# braids_v50.net
KiCad netlist of a schematic drawn in EAGLE
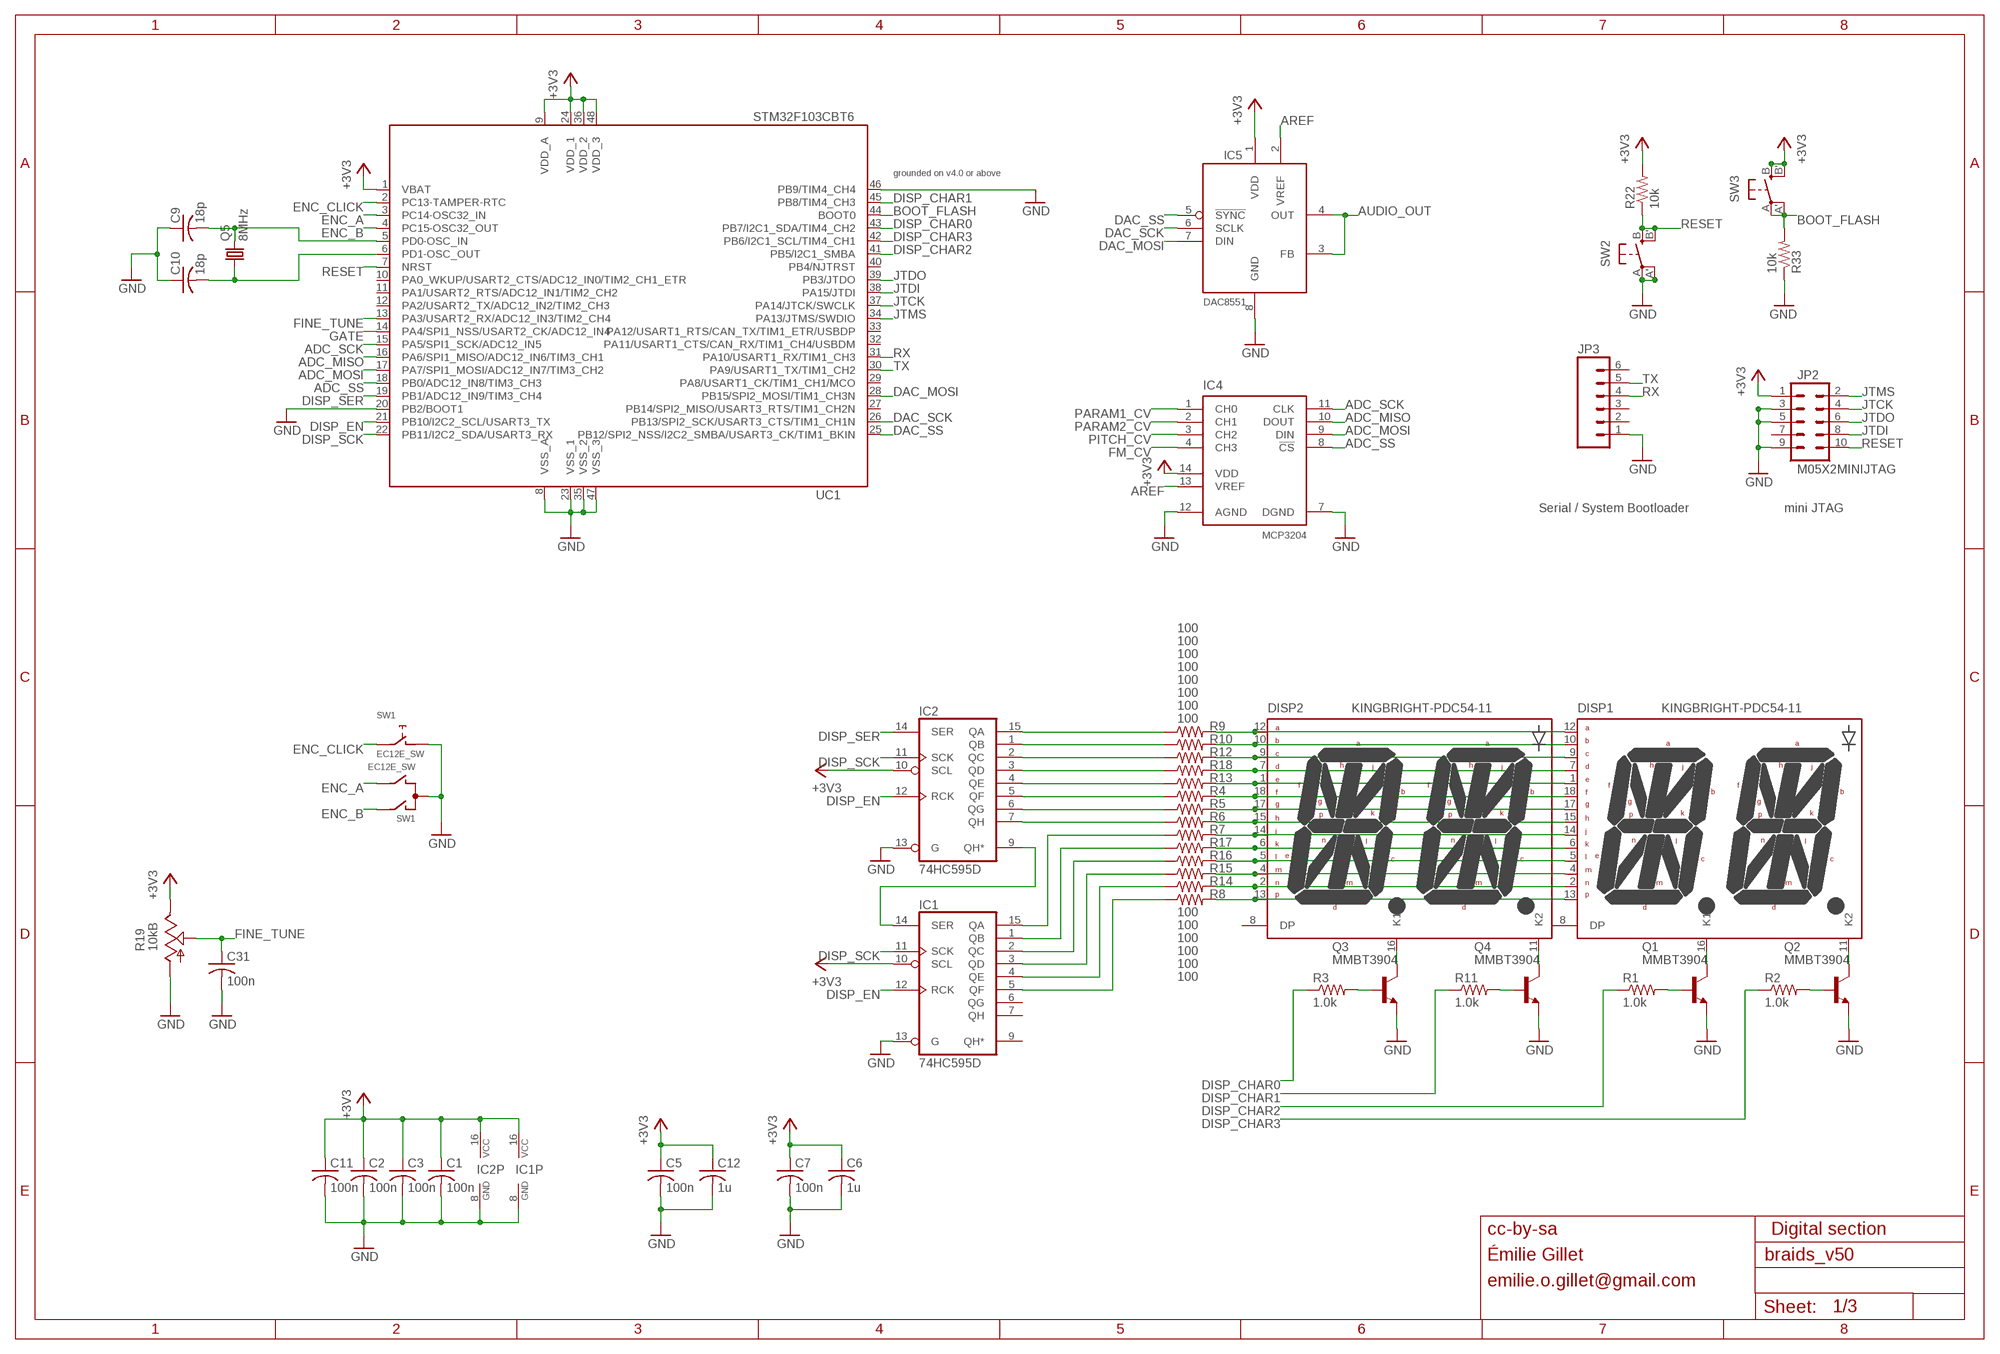
[diagram p0: schematic, sheet 1]
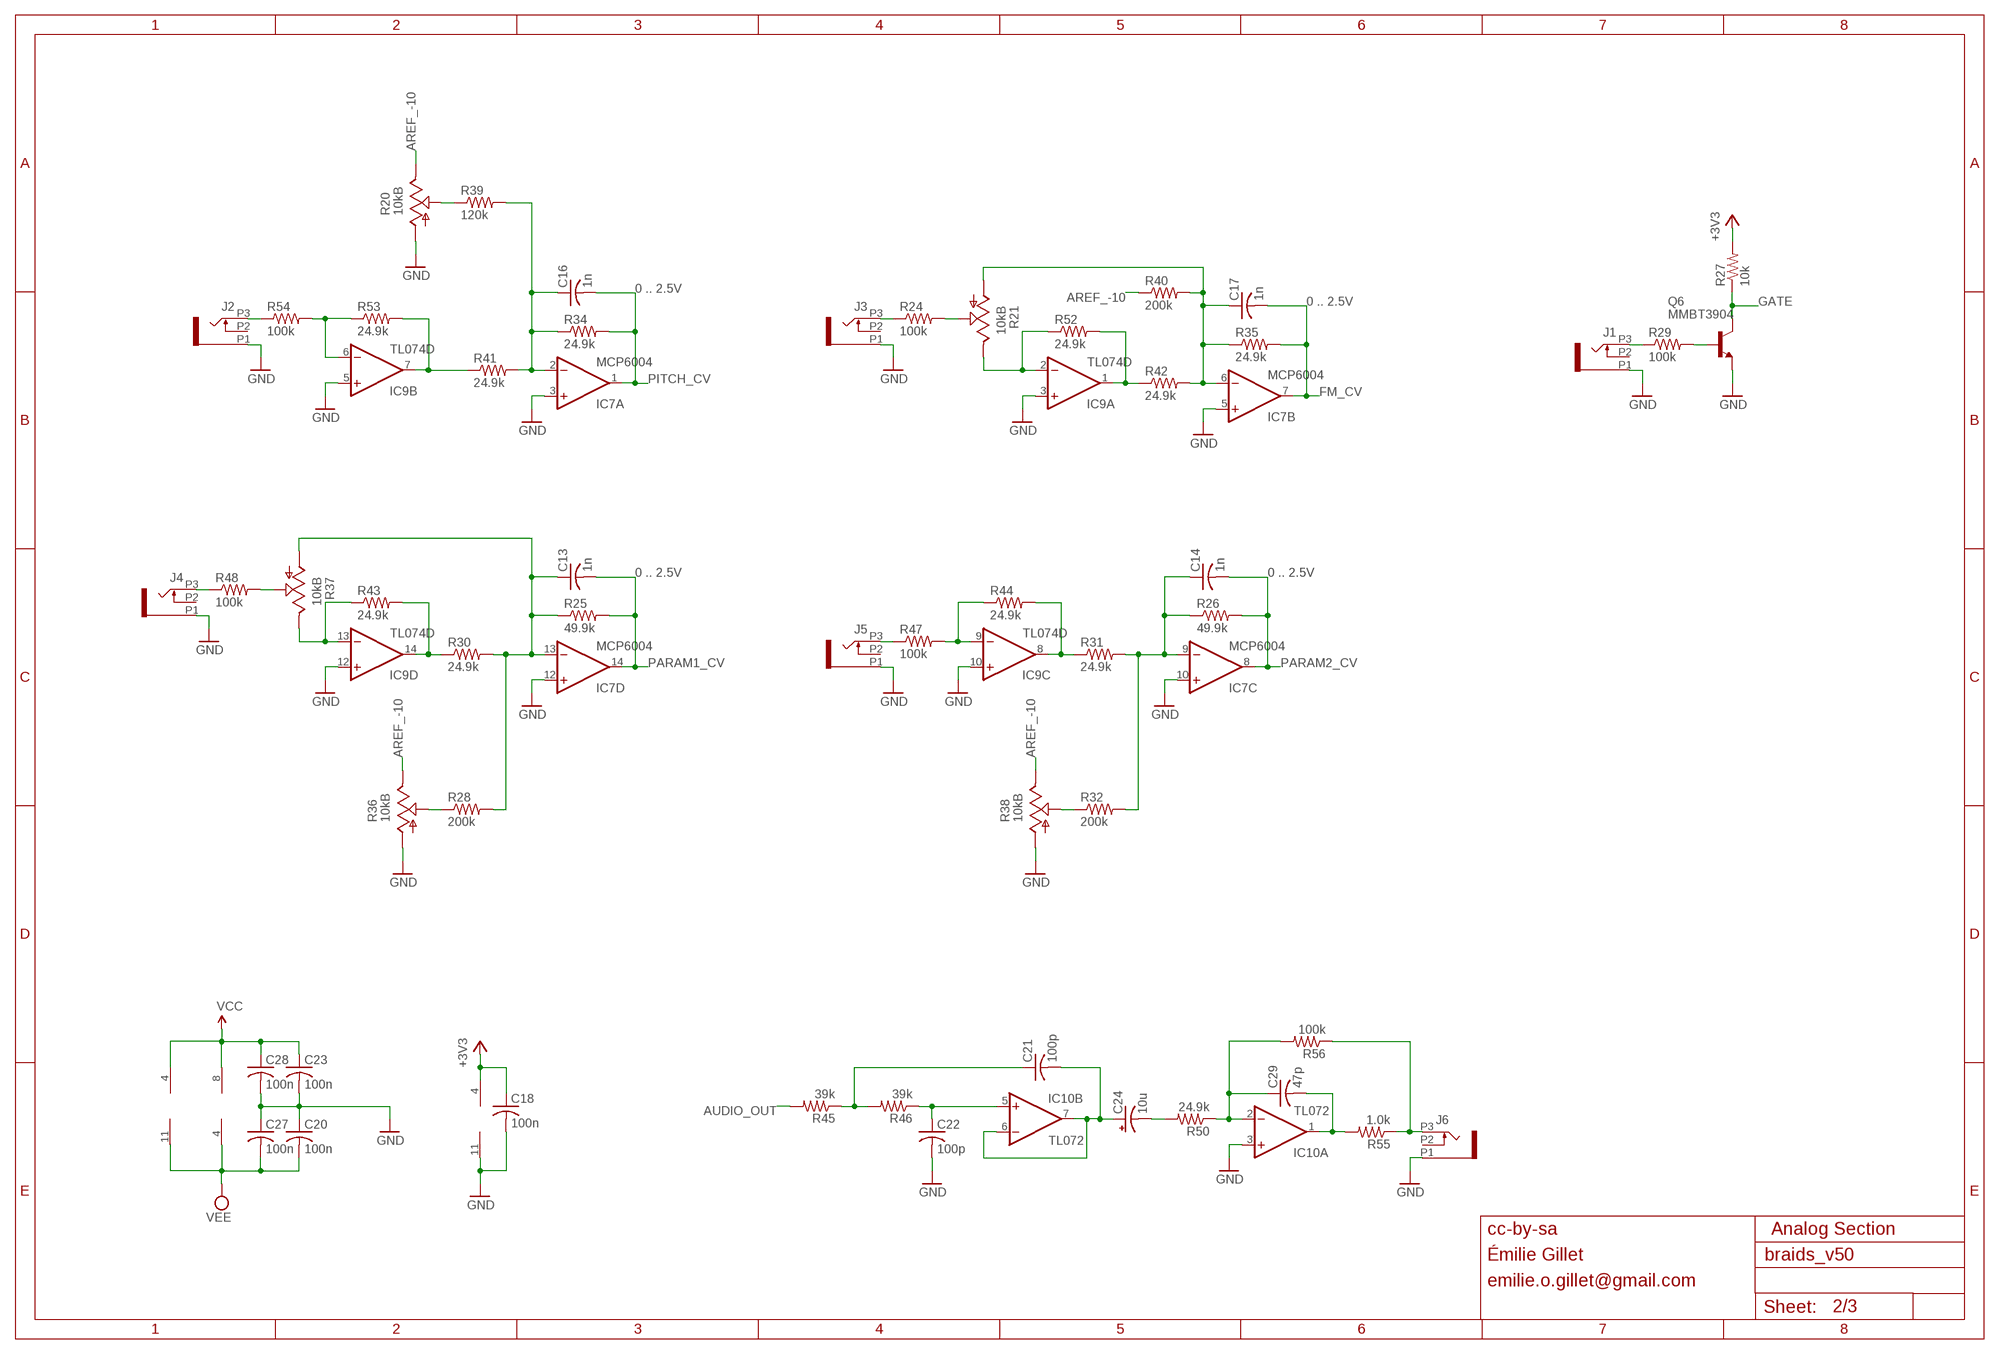
[diagram p1: schematic, sheet 2]
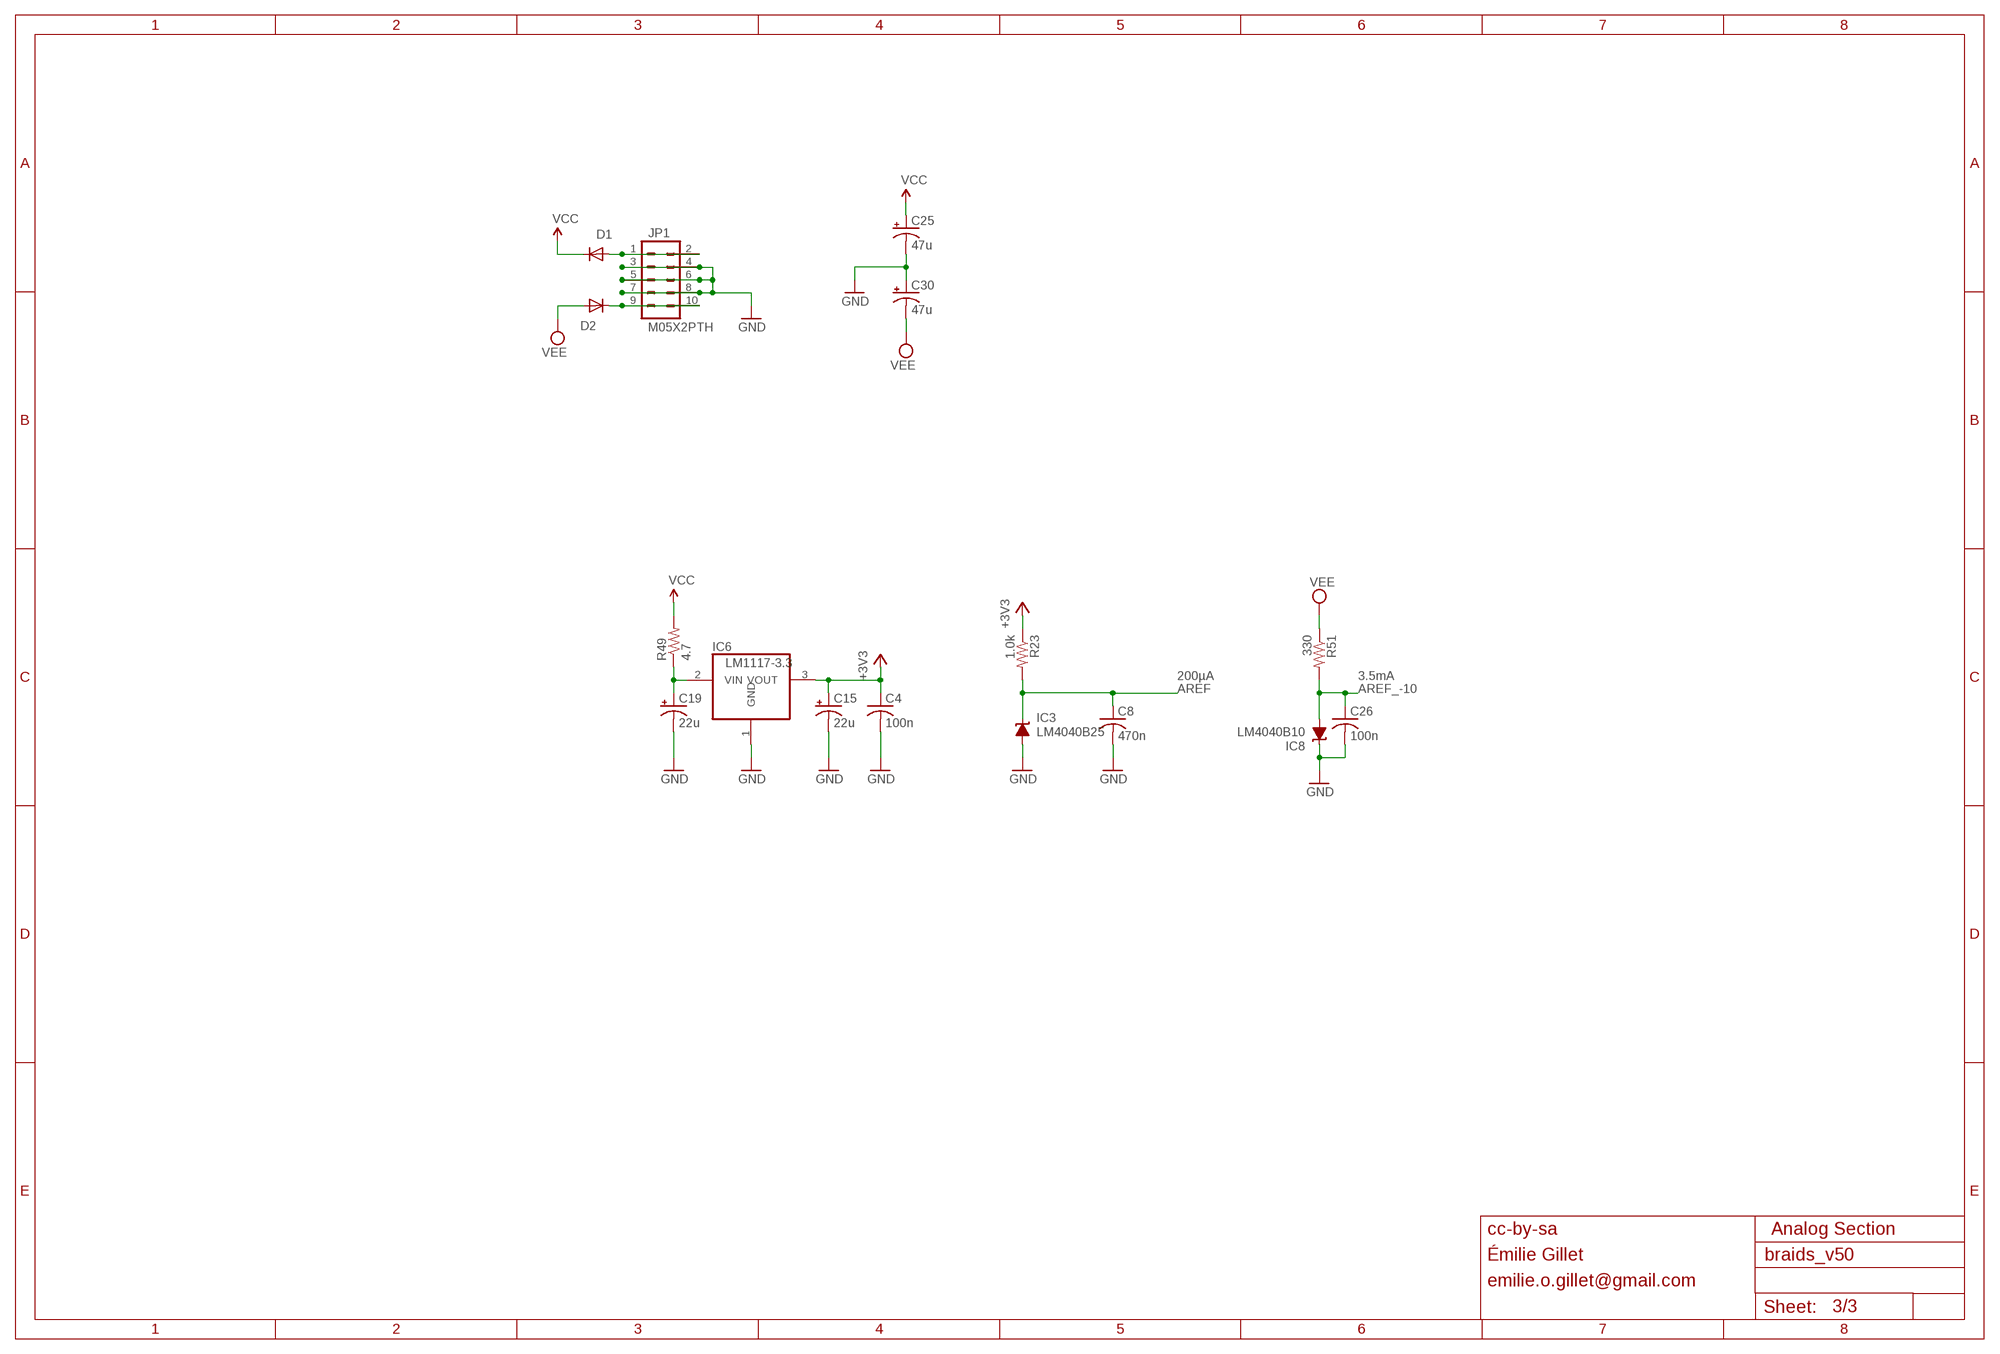
[diagram p2: schematic, sheet 3]

(export (version "E")
  (design (tool "Eeschema 10.0.6"))
  (components
    (comp (ref "C1")
      (value "100n")
      (footprint "eagle-import:C0603")
      (libsource (lib "eagle-import") (part "C-USC0603"))
    )
    (comp (ref "C2")
      (value "100n")
      (footprint "eagle-import:C0603")
      (libsource (lib "eagle-import") (part "C-USC0603"))
    )
    (comp (ref "C3")
      (value "100n")
      (footprint "eagle-import:C0603")
      (libsource (lib "eagle-import") (part "C-USC0603"))
    )
    (comp (ref "C5")
      (value "100n")
      (footprint "eagle-import:C0603")
      (libsource (lib "eagle-import") (part "C-USC0603"))
    )
    (comp (ref "C6")
      (value "1u")
      (footprint "eagle-import:C0603")
      (libsource (lib "eagle-import") (part "C-USC0603"))
    )
    (comp (ref "C7")
      (value "100n")
      (footprint "eagle-import:C0603")
      (libsource (lib "eagle-import") (part "C-USC0603"))
    )
    (comp (ref "C9")
      (value "18p")
      (footprint "eagle-import:C0603")
      (libsource (lib "eagle-import") (part "C-USC0603"))
    )
    (comp (ref "C10")
      (value "18p")
      (footprint "eagle-import:C0603")
      (libsource (lib "eagle-import") (part "C-USC0603"))
    )
    (comp (ref "C11")
      (value "100n")
      (footprint "eagle-import:C0603")
      (libsource (lib "eagle-import") (part "C-USC0603"))
    )
    (comp (ref "C12")
      (value "1u")
      (footprint "eagle-import:C0603")
      (libsource (lib "eagle-import") (part "C-USC0603"))
    )
    (comp (ref "C31")
      (value "100n")
      (footprint "eagle-import:C0603")
      (libsource (lib "eagle-import") (part "C-USC0603"))
    )
    (comp (ref "DISP1")
      (value "KINGBRIGHT-PDC54-11")
      (footprint "eagle-import:PDC54")
      (libsource (lib "eagle-import") (part "KINGBRIGHT-PDC54-11"))
    )
    (comp (ref "DISP2")
      (value "KINGBRIGHT-PDC54-11")
      (footprint "eagle-import:PDC54")
      (libsource (lib "eagle-import") (part "KINGBRIGHT-PDC54-11"))
    )
    (comp (ref "IC1")
      (value "74HC595D")
      (footprint "eagle-import:SO16")
      (libsource (lib "eagle-import") (part "74595DHC"))
    )
    (comp (ref "IC2")
      (value "74HC595D")
      (footprint "eagle-import:SO16")
      (libsource (lib "eagle-import") (part "74595DHC"))
    )
    (comp (ref "IC4")
      (value "MCP3204")
      (footprint "eagle-import:SO14")
      (libsource (lib "eagle-import") (part "MCP3302"))
    )
    (comp (ref "IC5")
      (value "DAC8551")
      (footprint "eagle-import:MSOP-8")
      (libsource (lib "eagle-import") (part "DAC855X"))
    )
    (comp (ref "JP2")
      (value "M05X2MINIJTAG")
      (footprint "eagle-import:2X5-1.27")
      (libsource (lib "eagle-import") (part "M05X2MINIJTAG"))
    )
    (comp (ref "JP3")
      (value "M06SIP")
      (footprint "eagle-import:1X06")
      (libsource (lib "eagle-import") (part "M06SIP"))
    )
    (comp (ref "Q1")
      (value "MMBT3904")
      (footprint "eagle-import:SOT23-BEC")
      (libsource (lib "eagle-import") (part "-NPN-SOT23-BECMMBT3904LT1"))
    )
    (comp (ref "Q2")
      (value "MMBT3904")
      (footprint "eagle-import:SOT23-BEC")
      (libsource (lib "eagle-import") (part "-NPN-SOT23-BECMMBT3904LT1"))
    )
    (comp (ref "Q3")
      (value "MMBT3904")
      (footprint "eagle-import:SOT23-BEC")
      (libsource (lib "eagle-import") (part "-NPN-SOT23-BECMMBT3904LT1"))
    )
    (comp (ref "Q4")
      (value "MMBT3904")
      (footprint "eagle-import:SOT23-BEC")
      (libsource (lib "eagle-import") (part "-NPN-SOT23-BECMMBT3904LT1"))
    )
    (comp (ref "Q5")
      (value "8MHz")
      (footprint "eagle-import:HC49UP")
      (libsource (lib "eagle-import") (part "CRYSTALHC49UP"))
    )
    (comp (ref "R1")
      (value "1.0k")
      (footprint "eagle-import:R0603")
      (libsource (lib "eagle-import") (part "R-US_R0603"))
    )
    (comp (ref "R2")
      (value "1.0k")
      (footprint "eagle-import:R0603")
      (libsource (lib "eagle-import") (part "R-US_R0603"))
    )
    (comp (ref "R3")
      (value "1.0k")
      (footprint "eagle-import:R0603")
      (libsource (lib "eagle-import") (part "R-US_R0603"))
    )
    (comp (ref "R4")
      (value "100")
      (footprint "eagle-import:R0603")
      (libsource (lib "eagle-import") (part "R-US_R0603"))
    )
    (comp (ref "R5")
      (value "100")
      (footprint "eagle-import:R0603")
      (libsource (lib "eagle-import") (part "R-US_R0603"))
    )
    (comp (ref "R6")
      (value "100")
      (footprint "eagle-import:R0603")
      (libsource (lib "eagle-import") (part "R-US_R0603"))
    )
    (comp (ref "R7")
      (value "100")
      (footprint "eagle-import:R0603")
      (libsource (lib "eagle-import") (part "R-US_R0603"))
    )
    (comp (ref "R8")
      (value "100")
      (footprint "eagle-import:R0603")
      (libsource (lib "eagle-import") (part "R-US_R0603"))
    )
    (comp (ref "R9")
      (value "100")
      (footprint "eagle-import:R0603")
      (libsource (lib "eagle-import") (part "R-US_R0603"))
    )
    (comp (ref "R10")
      (value "100")
      (footprint "eagle-import:R0603")
      (libsource (lib "eagle-import") (part "R-US_R0603"))
    )
    (comp (ref "R11")
      (value "1.0k")
      (footprint "eagle-import:R0603")
      (libsource (lib "eagle-import") (part "R-US_R0603"))
    )
    (comp (ref "R12")
      (value "100")
      (footprint "eagle-import:R0603")
      (libsource (lib "eagle-import") (part "R-US_R0603"))
    )
    (comp (ref "R13")
      (value "100")
      (footprint "eagle-import:R0603")
      (libsource (lib "eagle-import") (part "R-US_R0603"))
    )
    (comp (ref "R14")
      (value "100")
      (footprint "eagle-import:R0603")
      (libsource (lib "eagle-import") (part "R-US_R0603"))
    )
    (comp (ref "R15")
      (value "100")
      (footprint "eagle-import:R0603")
      (libsource (lib "eagle-import") (part "R-US_R0603"))
    )
    (comp (ref "R16")
      (value "100")
      (footprint "eagle-import:R0603")
      (libsource (lib "eagle-import") (part "R-US_R0603"))
    )
    (comp (ref "R17")
      (value "100")
      (footprint "eagle-import:R0603")
      (libsource (lib "eagle-import") (part "R-US_R0603"))
    )
    (comp (ref "R18")
      (value "100")
      (footprint "eagle-import:R0603")
      (libsource (lib "eagle-import") (part "R-US_R0603"))
    )
    (comp (ref "R19")
      (value "10kB")
      (footprint "eagle-import:ALPS_POT_VERTICAL_PS")
      (libsource (lib "eagle-import") (part "POT_USVERTICAL_PS"))
    )
    (comp (ref "R22")
      (value "10k")
      (footprint "eagle-import:R0603")
      (libsource (lib "eagle-import") (part "R-US_R0603"))
    )
    (comp (ref "R33")
      (value "10k")
      (footprint "eagle-import:R0603")
      (libsource (lib "eagle-import") (part "R-US_R0603"))
    )
    (comp (ref "SW1")
      (value "EC12E_SW")
      (footprint "eagle-import:ALPS_EC12E_SW")
      (libsource (lib "eagle-import") (part "EC12E_SW"))
    )
    (comp (ref "SW2")
      (value "EVQQ2")
      (footprint "eagle-import:EVQ-Q2")
      (libsource (lib "eagle-import") (part "EVQQ2"))
    )
    (comp (ref "SW3")
      (value "EVQQ2")
      (footprint "eagle-import:EVQ-Q2")
      (libsource (lib "eagle-import") (part "EVQQ2"))
    )
    (comp (ref "UC1")
      (value "STM32F103CBT6")
      (footprint "eagle-import:LQFP48")
      (libsource (lib "eagle-import") (part "STM32F103CB"))
    )
    (comp (ref "C4")
      (value "100n")
      (footprint "eagle-import:C0603")
      (libsource (lib "eagle-import") (part "C-USC0603"))
    )
    (comp (ref "C8")
      (value "470n")
      (footprint "eagle-import:C0603")
      (libsource (lib "eagle-import") (part "C-USC0603"))
    )
    (comp (ref "C15")
      (value "22u")
      (footprint "eagle-import:PANASONIC_C")
      (libsource (lib "eagle-import") (part "CPOL-USC"))
    )
    (comp (ref "C19")
      (value "22u")
      (footprint "eagle-import:PANASONIC_C")
      (libsource (lib "eagle-import") (part "CPOL-USC"))
    )
    (comp (ref "C25")
      (value "47u")
      (footprint "eagle-import:PANASONIC_D")
      (libsource (lib "eagle-import") (part "CPOL-USD"))
    )
    (comp (ref "C26")
      (value "100n")
      (footprint "eagle-import:C0603")
      (libsource (lib "eagle-import") (part "C-USC0603"))
    )
    (comp (ref "C30")
      (value "47u")
      (footprint "eagle-import:PANASONIC_D")
      (libsource (lib "eagle-import") (part "CPOL-USD"))
    )
    (comp (ref "D1")
      (value "1N5819HW")
      (footprint "eagle-import:SOD123")
      (libsource (lib "eagle-import") (part "DIODE-SOD123"))
    )
    (comp (ref "D2")
      (value "1N5819HW")
      (footprint "eagle-import:SOD123")
      (libsource (lib "eagle-import") (part "DIODE-SOD123"))
    )
    (comp (ref "IC3")
      (value "LM4040B25")
      (footprint "eagle-import:DBZ_R-PDSO-G3")
      (libsource (lib "eagle-import") (part "LM4041DBZB12"))
    )
    (comp (ref "IC6")
      (value "LM1117-3.3")
      (footprint "eagle-import:TO252")
      (libsource (lib "eagle-import") (part "REG1117T"))
    )
    (comp (ref "IC8")
      (value "LM4040B10")
      (footprint "eagle-import:DBZ_R-PDSO-G3")
      (libsource (lib "eagle-import") (part "LM4041DBZB12"))
    )
    (comp (ref "JP1")
      (value "M05X2PTH")
      (footprint "eagle-import:AVR_ICSP")
      (libsource (lib "eagle-import") (part "M05X2PTH"))
    )
    (comp (ref "R23")
      (value "1.0k")
      (footprint "eagle-import:R0603")
      (libsource (lib "eagle-import") (part "R-US_R0603"))
    )
    (comp (ref "R49")
      (value "4.7")
      (footprint "eagle-import:R1206")
      (libsource (lib "eagle-import") (part "R-US_R1206"))
    )
    (comp (ref "R51")
      (value "330")
      (footprint "eagle-import:R0603")
      (libsource (lib "eagle-import") (part "R-US_R0603"))
    )
    (comp (ref "C13")
      (value "1n")
      (footprint "eagle-import:C0603")
      (libsource (lib "eagle-import") (part "C-USC0603"))
    )
    (comp (ref "C14")
      (value "1n")
      (footprint "eagle-import:C0603")
      (libsource (lib "eagle-import") (part "C-USC0603"))
    )
    (comp (ref "C16")
      (value "1n")
      (footprint "eagle-import:C0603")
      (libsource (lib "eagle-import") (part "C-USC0603"))
    )
    (comp (ref "C17")
      (value "1n")
      (footprint "eagle-import:C0603")
      (libsource (lib "eagle-import") (part "C-USC0603"))
    )
    (comp (ref "C18")
      (value "100n")
      (footprint "eagle-import:C0603")
      (libsource (lib "eagle-import") (part "C-USC0603"))
    )
    (comp (ref "C20")
      (value "100n")
      (footprint "eagle-import:C0603")
      (libsource (lib "eagle-import") (part "C-USC0603"))
    )
    (comp (ref "C21")
      (value "100p")
      (footprint "eagle-import:C0603")
      (libsource (lib "eagle-import") (part "C-USC0603"))
    )
    (comp (ref "C22")
      (value "100p")
      (footprint "eagle-import:C0603")
      (libsource (lib "eagle-import") (part "C-USC0603"))
    )
    (comp (ref "C23")
      (value "100n")
      (footprint "eagle-import:C0603")
      (libsource (lib "eagle-import") (part "C-USC0603"))
    )
    (comp (ref "C24")
      (value "10u")
      (footprint "eagle-import:PANASONIC_B")
      (libsource (lib "eagle-import") (part "CPOL-USB"))
    )
    (comp (ref "C27")
      (value "100n")
      (footprint "eagle-import:C0603")
      (libsource (lib "eagle-import") (part "C-USC0603"))
    )
    (comp (ref "C28")
      (value "100n")
      (footprint "eagle-import:C0603")
      (libsource (lib "eagle-import") (part "C-USC0603"))
    )
    (comp (ref "C29")
      (value "47p")
      (footprint "eagle-import:C0603")
      (libsource (lib "eagle-import") (part "C-USC0603"))
    )
    (comp (ref "IC7")
      (value "MCP6004")
      (footprint "eagle-import:SO14")
      (libsource (lib "eagle-import") (part "TL074D"))
    )
    (comp (ref "IC9")
      (value "TL074D")
      (footprint "eagle-import:SO14")
      (libsource (lib "eagle-import") (part "TL074D"))
    )
    (comp (ref "IC10")
      (value "TL072")
      (footprint "eagle-import:SO08")
      (libsource (lib "eagle-import") (part "TL072D"))
    )
    (comp (ref "J1")
      (value "PJ301_THONKICONN6")
      (footprint "eagle-import:WQP_PJ_301M6")
      (libsource (lib "eagle-import") (part "PJ301_THONKICONN6"))
    )
    (comp (ref "J2")
      (value "PJ301_THONKICONN6")
      (footprint "eagle-import:WQP_PJ_301M6")
      (libsource (lib "eagle-import") (part "PJ301_THONKICONN6"))
    )
    (comp (ref "J3")
      (value "PJ301_THONKICONN6")
      (footprint "eagle-import:WQP_PJ_301M6")
      (libsource (lib "eagle-import") (part "PJ301_THONKICONN6"))
    )
    (comp (ref "J4")
      (value "PJ301_THONKICONN6")
      (footprint "eagle-import:WQP_PJ_301M6")
      (libsource (lib "eagle-import") (part "PJ301_THONKICONN6"))
    )
    (comp (ref "J5")
      (value "PJ301_THONKICONN6")
      (footprint "eagle-import:WQP_PJ_301M6")
      (libsource (lib "eagle-import") (part "PJ301_THONKICONN6"))
    )
    (comp (ref "J6")
      (value "PJ301_THONKICONN6")
      (footprint "eagle-import:WQP_PJ_301M6")
      (libsource (lib "eagle-import") (part "PJ301_THONKICONN6"))
    )
    (comp (ref "Q6")
      (value "MMBT3904")
      (footprint "eagle-import:SOT23-BEC")
      (libsource (lib "eagle-import") (part "-NPN-SOT23-BECMMBT3904LT1"))
    )
    (comp (ref "R20")
      (value "10kB")
      (footprint "eagle-import:ALPS_POT_VERTICAL_PS")
      (libsource (lib "eagle-import") (part "POT_USVERTICAL_PS"))
    )
    (comp (ref "R21")
      (value "10kB")
      (footprint "eagle-import:ALPS_POT_VERTICAL_PS")
      (libsource (lib "eagle-import") (part "POT_USVERTICAL_PS"))
    )
    (comp (ref "R24")
      (value "100k")
      (footprint "eagle-import:R0603")
      (libsource (lib "eagle-import") (part "R-US_R0603"))
    )
    (comp (ref "R25")
      (value "49.9k")
      (footprint "eagle-import:R0603")
      (libsource (lib "eagle-import") (part "R-US_R0603"))
    )
    (comp (ref "R26")
      (value "49.9k")
      (footprint "eagle-import:R0603")
      (libsource (lib "eagle-import") (part "R-US_R0603"))
    )
    (comp (ref "R27")
      (value "10k")
      (footprint "eagle-import:R0603")
      (libsource (lib "eagle-import") (part "R-US_R0603"))
    )
    (comp (ref "R28")
      (value "200k")
      (footprint "eagle-import:R0603")
      (libsource (lib "eagle-import") (part "R-US_R0603"))
    )
    (comp (ref "R29")
      (value "100k")
      (footprint "eagle-import:R0603")
      (libsource (lib "eagle-import") (part "R-US_R0603"))
    )
    (comp (ref "R30")
      (value "24.9k")
      (footprint "eagle-import:R0603")
      (libsource (lib "eagle-import") (part "R-US_R0603"))
    )
    (comp (ref "R31")
      (value "24.9k")
      (footprint "eagle-import:R0603")
      (libsource (lib "eagle-import") (part "R-US_R0603"))
    )
    (comp (ref "R32")
      (value "200k")
      (footprint "eagle-import:R0603")
      (libsource (lib "eagle-import") (part "R-US_R0603"))
    )
    (comp (ref "R34")
      (value "24.9k")
      (footprint "eagle-import:R0603")
      (libsource (lib "eagle-import") (part "R-US_R0603"))
    )
    (comp (ref "R35")
      (value "24.9k")
      (footprint "eagle-import:R0603")
      (libsource (lib "eagle-import") (part "R-US_R0603"))
    )
    (comp (ref "R36")
      (value "10kB")
      (footprint "eagle-import:ALPS_POT_VERTICAL_PS")
      (libsource (lib "eagle-import") (part "POT_USVERTICAL_PS"))
    )
    (comp (ref "R37")
      (value "10kB")
      (footprint "eagle-import:ALPS_POT_VERTICAL_PS")
      (libsource (lib "eagle-import") (part "POT_USVERTICAL_PS"))
    )
    (comp (ref "R38")
      (value "10kB")
      (footprint "eagle-import:ALPS_POT_VERTICAL_PS")
      (libsource (lib "eagle-import") (part "POT_USVERTICAL_PS"))
    )
    (comp (ref "R39")
      (value "120k")
      (footprint "eagle-import:R0603")
      (libsource (lib "eagle-import") (part "R-US_R0603"))
    )
    (comp (ref "R40")
      (value "200k")
      (footprint "eagle-import:R0603")
      (libsource (lib "eagle-import") (part "R-US_R0603"))
    )
    (comp (ref "R41")
      (value "24.9k")
      (footprint "eagle-import:R0603")
      (libsource (lib "eagle-import") (part "R-US_R0603"))
    )
    (comp (ref "R42")
      (value "24.9k")
      (footprint "eagle-import:R0603")
      (libsource (lib "eagle-import") (part "R-US_R0603"))
    )
    (comp (ref "R43")
      (value "24.9k")
      (footprint "eagle-import:R0603")
      (libsource (lib "eagle-import") (part "R-US_R0603"))
    )
    (comp (ref "R44")
      (value "24.9k")
      (footprint "eagle-import:R0603")
      (libsource (lib "eagle-import") (part "R-US_R0603"))
    )
    (comp (ref "R45")
      (value "39k")
      (footprint "eagle-import:R0603")
      (libsource (lib "eagle-import") (part "R-US_R0603"))
    )
    (comp (ref "R46")
      (value "39k")
      (footprint "eagle-import:R0603")
      (libsource (lib "eagle-import") (part "R-US_R0603"))
    )
    (comp (ref "R47")
      (value "100k")
      (footprint "eagle-import:R0603")
      (libsource (lib "eagle-import") (part "R-US_R0603"))
    )
    (comp (ref "R48")
      (value "100k")
      (footprint "eagle-import:R0603")
      (libsource (lib "eagle-import") (part "R-US_R0603"))
    )
    (comp (ref "R50")
      (value "24.9k")
      (footprint "eagle-import:R0603")
      (libsource (lib "eagle-import") (part "R-US_R0603"))
    )
    (comp (ref "R52")
      (value "24.9k")
      (footprint "eagle-import:R0603")
      (libsource (lib "eagle-import") (part "R-US_R0603"))
    )
    (comp (ref "R53")
      (value "24.9k")
      (footprint "eagle-import:R0603")
      (libsource (lib "eagle-import") (part "R-US_R0603"))
    )
    (comp (ref "R54")
      (value "100k")
      (footprint "eagle-import:R0603")
      (libsource (lib "eagle-import") (part "R-US_R0603"))
    )
    (comp (ref "R55")
      (value "1.0k")
      (footprint "eagle-import:R0603")
      (libsource (lib "eagle-import") (part "R-US_R0603"))
    )
    (comp (ref "R56")
      (value "100k")
      (footprint "eagle-import:R0603")
      (libsource (lib "eagle-import") (part "R-US_R0603"))
    )
  )
  (nets
    (net (code "1") (name "+3V3") (class "Default")
      (node (ref "C1") (pin "1") (pinfunction "1_1") (pintype "passive"))
      (node (ref "C11") (pin "1") (pinfunction "1_1") (pintype "passive"))
      (node (ref "C12") (pin "1") (pinfunction "1_1") (pintype "passive"))
      (node (ref "C15") (pin "+") (pinfunction "+_+") (pintype "passive"))
      (node (ref "C18") (pin "1") (pinfunction "1_1") (pintype "passive"))
      (node (ref "C2") (pin "1") (pinfunction "1_1") (pintype "passive"))
      (node (ref "C3") (pin "1") (pinfunction "1_1") (pintype "passive"))
      (node (ref "C4") (pin "1") (pinfunction "1_1") (pintype "passive"))
      (node (ref "C5") (pin "1") (pinfunction "1_1") (pintype "passive"))
      (node (ref "C6") (pin "1") (pinfunction "1_1") (pintype "passive"))
      (node (ref "C7") (pin "1") (pinfunction "1_1") (pintype "passive"))
      (node (ref "IC1") (pin "10") (pinfunction "SCL_10") (pintype "input"))
      (node (ref "IC1") (pin "16") (pinfunction "VCC_16") (pintype "power_in"))
      (node (ref "IC2") (pin "10") (pinfunction "SCL_10") (pintype "input"))
      (node (ref "IC2") (pin "16") (pinfunction "VCC_16") (pintype "power_in"))
      (node (ref "IC4") (pin "14") (pinfunction "VDD_14") (pintype "bidirectional"))
      (node (ref "IC5") (pin "1") (pinfunction "VDD_1") (pintype "power_in"))
      (node (ref "IC6") (pin "3") (pinfunction "VOUT_3") (pintype "output"))
      (node (ref "IC7") (pin "4") (pinfunction "V+_4") (pintype "power_in"))
      (node (ref "JP2") (pin "1") (pinfunction "1_1") (pintype "passive"))
      (node (ref "R19") (pin "P$1") (pinfunction "E_P$1") (pintype "passive"))
      (node (ref "R22") (pin "2") (pinfunction "2_2") (pintype "passive"))
      (node (ref "R23") (pin "1") (pinfunction "1_1") (pintype "passive"))
      (node (ref "R27") (pin "2") (pinfunction "2_2") (pintype "passive"))
      (node (ref "SW3") (pin "B") (pinfunction "S_B") (pintype "passive"))
      (node (ref "SW3") (pin "B'") (pinfunction "S1_B'") (pintype "passive"))
      (node (ref "UC1") (pin "1") (pinfunction "VBAT_1") (pintype "power_in"))
      (node (ref "UC1") (pin "24") (pinfunction "VDD_1_24") (pintype "power_in"))
      (node (ref "UC1") (pin "36") (pinfunction "VDD_2_36") (pintype "power_in"))
      (node (ref "UC1") (pin "48") (pinfunction "VDD_3_48") (pintype "power_in"))
      (node (ref "UC1") (pin "9") (pinfunction "VDD_A_9") (pintype "power_in"))
    )
    (net (code "2") (name "ADC_MISO") (class "Default")
      (node (ref "IC4") (pin "10") (pinfunction "DOUT_10") (pintype "bidirectional"))
      (node (ref "UC1") (pin "16") (pinfunction "PA6/SPI1_MISO/ADC12_IN6/TIM3_CH1_16") (pintype "bidirectional"))
    )
    (net (code "3") (name "ADC_MOSI") (class "Default")
      (node (ref "IC4") (pin "9") (pinfunction "DIN_9") (pintype "bidirectional"))
      (node (ref "UC1") (pin "17") (pinfunction "PA7/SPI1_MOSI/ADC12_IN7/TIM3_CH2_17") (pintype "bidirectional"))
    )
    (net (code "4") (name "ADC_SCK") (class "Default")
      (node (ref "IC4") (pin "11") (pinfunction "CLK_11") (pintype "bidirectional"))
      (node (ref "UC1") (pin "15") (pinfunction "PA5/SPI1_SCK/ADC12_IN5_15") (pintype "bidirectional"))
    )
    (net (code "5") (name "ADC_SS") (class "Default")
      (node (ref "IC4") (pin "8") (pinfunction "~{CS}_8") (pintype "bidirectional"))
      (node (ref "UC1") (pin "18") (pinfunction "PB0/ADC12_IN8/TIM3_CH3_18") (pintype "bidirectional"))
    )
    (net (code "6") (name "AREF") (class "Default")
      (node (ref "C8") (pin "1") (pinfunction "1_1") (pintype "passive"))
      (node (ref "IC3") (pin "1") (pinfunction "C_1") (pintype "passive"))
      (node (ref "IC4") (pin "13") (pinfunction "VREF_13") (pintype "bidirectional"))
      (node (ref "IC5") (pin "2") (pinfunction "VREF_2") (pintype "power_in"))
      (node (ref "R23") (pin "2") (pinfunction "2_2") (pintype "passive"))
    )
    (net (code "7") (name "AREF_-10") (class "Default")
      (node (ref "C26") (pin "1") (pinfunction "1_1") (pintype "passive"))
      (node (ref "IC8") (pin "2") (pinfunction "A_2") (pintype "passive"))
      (node (ref "R20") (pin "P$1") (pinfunction "E_P$1") (pintype "passive"))
      (node (ref "R36") (pin "P$1") (pinfunction "E_P$1") (pintype "passive"))
      (node (ref "R38") (pin "P$1") (pinfunction "E_P$1") (pintype "passive"))
      (node (ref "R40") (pin "1") (pinfunction "1_1") (pintype "passive"))
      (node (ref "R51") (pin "2") (pinfunction "2_2") (pintype "passive"))
    )
    (net (code "8") (name "AUDIO_OUT") (class "Default")
      (node (ref "IC5") (pin "3") (pinfunction "FB_3") (pintype "input"))
      (node (ref "IC5") (pin "4") (pinfunction "OUT_4") (pintype "output"))
      (node (ref "R45") (pin "2") (pinfunction "2_2") (pintype "passive"))
    )
    (net (code "9") (name "BOOT_FLASH") (class "Default")
      (node (ref "R33") (pin "2") (pinfunction "2_2") (pintype "passive"))
      (node (ref "SW3") (pin "A") (pinfunction "P_A") (pintype "passive"))
      (node (ref "SW3") (pin "A'") (pinfunction "P1_A'") (pintype "passive"))
      (node (ref "UC1") (pin "44") (pinfunction "BOOT0_44") (pintype "input"))
    )
    (net (code "10") (name "DAC_MOSI") (class "Default")
      (node (ref "IC5") (pin "7") (pinfunction "DIN_7") (pintype "bidirectional"))
      (node (ref "UC1") (pin "28") (pinfunction "PB15/SPI2_MOSI/TIM1_CH3N_28") (pintype "input"))
    )
    (net (code "11") (name "DAC_SCK") (class "Default")
      (node (ref "IC5") (pin "6") (pinfunction "SCLK_6") (pintype "bidirectional"))
      (node (ref "UC1") (pin "26") (pinfunction "PB13/SPI2_SCK/USART3_CTS/TIM1_CH1N_26") (pintype "input"))
    )
    (net (code "12") (name "DAC_SS") (class "Default")
      (node (ref "IC5") (pin "5") (pinfunction "~{SYNC}_5") (pintype "bidirectional"))
      (node (ref "UC1") (pin "25") (pinfunction "PB12/SPI2_NSS/I2C2_SMBA/USART3_CK/TIM1_BKIN_25") (pintype "input"))
    )
    (net (code "13") (name "DISP_CHAR0") (class "Default")
      (node (ref "R3") (pin "1") (pinfunction "1_1") (pintype "passive"))
      (node (ref "UC1") (pin "43") (pinfunction "PB7/I2C1_SDA/TIM4_CH2_43") (pintype "bidirectional"))
    )
    (net (code "14") (name "DISP_CHAR1") (class "Default")
      (node (ref "R11") (pin "1") (pinfunction "1_1") (pintype "passive"))
      (node (ref "UC1") (pin "45") (pinfunction "PB8/TIM4_CH3_45") (pintype "bidirectional"))
    )
    (net (code "15") (name "DISP_CHAR2") (class "Default")
      (node (ref "R1") (pin "1") (pinfunction "1_1") (pintype "passive"))
      (node (ref "UC1") (pin "41") (pinfunction "PB5/I2C1_SMBA_41") (pintype "input"))
    )
    (net (code "16") (name "DISP_CHAR3") (class "Default")
      (node (ref "R2") (pin "1") (pinfunction "1_1") (pintype "passive"))
      (node (ref "UC1") (pin "42") (pinfunction "PB6/I2C1_SCL/TIM4_CH1_42") (pintype "input"))
    )
    (net (code "17") (name "DISP_EN") (class "Default")
      (node (ref "IC1") (pin "12") (pinfunction "RCK_12") (pintype "input"))
      (node (ref "IC2") (pin "12") (pinfunction "RCK_12") (pintype "input"))
      (node (ref "UC1") (pin "21") (pinfunction "PB10/I2C2_SCL/USART3_TX_21") (pintype "input"))
    )
    (net (code "18") (name "DISP_SCK") (class "Default")
      (node (ref "IC1") (pin "11") (pinfunction "SCK_11") (pintype "input"))
      (node (ref "IC2") (pin "11") (pinfunction "SCK_11") (pintype "input"))
      (node (ref "UC1") (pin "22") (pinfunction "PB11/I2C2_SDA/USART3_RX_22") (pintype "input"))
    )
    (net (code "19") (name "DISP_SER") (class "Default")
      (node (ref "IC2") (pin "14") (pinfunction "SER_14") (pintype "input"))
      (node (ref "UC1") (pin "19") (pinfunction "PB1/ADC12_IN9/TIM3_CH4_19") (pintype "bidirectional"))
    )
    (net (code "20") (name "ENC_A") (class "Default")
      (node (ref "SW1") (pin "B") (pinfunction "B_B") (pintype "passive"))
      (node (ref "UC1") (pin "3") (pinfunction "PC14-OSC32_IN_3") (pintype "input"))
    )
    (net (code "21") (name "ENC_B") (class "Default")
      (node (ref "SW1") (pin "A") (pinfunction "A_A") (pintype "passive"))
      (node (ref "UC1") (pin "4") (pinfunction "PC15-OSC32_OUT_4") (pintype "input"))
    )
    (net (code "22") (name "ENC_CLICK") (class "Default")
      (node (ref "SW1") (pin "E") (pinfunction "2_E") (pintype "passive"))
      (node (ref "UC1") (pin "2") (pinfunction "PC13-TAMPER-RTC_2") (pintype "input"))
    )
    (net (code "23") (name "FINE_TUNE") (class "Default")
      (node (ref "C31") (pin "1") (pinfunction "1_1") (pintype "passive"))
      (node (ref "R19") (pin "P$2") (pinfunction "S_P$2") (pintype "passive"))
      (node (ref "UC1") (pin "13") (pinfunction "PA3/USART2_RX/ADC12_IN3/TIM2_CH4_13") (pintype "bidirectional"))
    )
    (net (code "24") (name "FM_CV") (class "Default")
      (node (ref "C17") (pin "2") (pinfunction "2_2") (pintype "passive"))
      (node (ref "IC4") (pin "4") (pinfunction "CH3_4") (pintype "bidirectional"))
      (node (ref "IC7") (pin "7") (pinfunction "OUT_7") (pintype "output"))
      (node (ref "R35") (pin "2") (pinfunction "2_2") (pintype "passive"))
    )
    (net (code "25") (name "GATE") (class "Default")
      (node (ref "Q6") (pin "C") (pinfunction "C_C") (pintype "passive"))
      (node (ref "R27") (pin "1") (pinfunction "1_1") (pintype "passive"))
      (node (ref "UC1") (pin "14") (pinfunction "PA4/SPI1_NSS/USART2_CK/ADC12_IN4_14") (pintype "bidirectional"))
    )
    (net (code "26") (name "GND") (class "Default")
      (node (ref "C1") (pin "2") (pinfunction "2_2") (pintype "passive"))
      (node (ref "C10") (pin "1") (pinfunction "1_1") (pintype "passive"))
      (node (ref "C11") (pin "2") (pinfunction "2_2") (pintype "passive"))
      (node (ref "C12") (pin "2") (pinfunction "2_2") (pintype "passive"))
      (node (ref "C15") (pin "-") (pinfunction "-_-") (pintype "passive"))
      (node (ref "C18") (pin "2") (pinfunction "2_2") (pintype "passive"))
      (node (ref "C19") (pin "-") (pinfunction "-_-") (pintype "passive"))
      (node (ref "C2") (pin "2") (pinfunction "2_2") (pintype "passive"))
      (node (ref "C20") (pin "1") (pinfunction "1_1") (pintype "passive"))
      (node (ref "C22") (pin "2") (pinfunction "2_2") (pintype "passive"))
      (node (ref "C23") (pin "2") (pinfunction "2_2") (pintype "passive"))
      (node (ref "C25") (pin "-") (pinfunction "-_-") (pintype "passive"))
      (node (ref "C26") (pin "2") (pinfunction "2_2") (pintype "passive"))
      (node (ref "C27") (pin "1") (pinfunction "1_1") (pintype "passive"))
      (node (ref "C28") (pin "2") (pinfunction "2_2") (pintype "passive"))
      (node (ref "C3") (pin "2") (pinfunction "2_2") (pintype "passive"))
      (node (ref "C30") (pin "+") (pinfunction "+_+") (pintype "passive"))
      (node (ref "C31") (pin "2") (pinfunction "2_2") (pintype "passive"))
      (node (ref "C4") (pin "2") (pinfunction "2_2") (pintype "passive"))
      (node (ref "C5") (pin "2") (pinfunction "2_2") (pintype "passive"))
      (node (ref "C6") (pin "2") (pinfunction "2_2") (pintype "passive"))
      (node (ref "C7") (pin "2") (pinfunction "2_2") (pintype "passive"))
      (node (ref "C8") (pin "2") (pinfunction "2_2") (pintype "passive"))
      (node (ref "C9") (pin "1") (pinfunction "1_1") (pintype "passive"))
      (node (ref "IC1") (pin "13") (pinfunction "G_13") (pintype "input"))
      (node (ref "IC1") (pin "8") (pinfunction "GND_8") (pintype "power_in"))
      (node (ref "IC10") (pin "3") (pinfunction "+IN_3") (pintype "input"))
      (node (ref "IC2") (pin "13") (pinfunction "G_13") (pintype "input"))
      (node (ref "IC2") (pin "8") (pinfunction "GND_8") (pintype "power_in"))
      (node (ref "IC3") (pin "2") (pinfunction "A_2") (pintype "passive"))
      (node (ref "IC4") (pin "12") (pinfunction "AGND_12") (pintype "bidirectional"))
      (node (ref "IC4") (pin "7") (pinfunction "DGND_7") (pintype "bidirectional"))
      (node (ref "IC5") (pin "8") (pinfunction "GND_8") (pintype "power_in"))
      (node (ref "IC6") (pin "1") (pinfunction "GND_1") (pintype "power_in"))
      (node (ref "IC7") (pin "10") (pinfunction "+IN_10") (pintype "input"))
      (node (ref "IC7") (pin "11") (pinfunction "V-_11") (pintype "power_in"))
      (node (ref "IC7") (pin "12") (pinfunction "+IN_12") (pintype "input"))
      (node (ref "IC7") (pin "3") (pinfunction "+IN_3") (pintype "input"))
      (node (ref "IC7") (pin "5") (pinfunction "+IN_5") (pintype "input"))
      (node (ref "IC8") (pin "1") (pinfunction "C_1") (pintype "passive"))
      (node (ref "IC9") (pin "10") (pinfunction "+IN_10") (pintype "input"))
      (node (ref "IC9") (pin "12") (pinfunction "+IN_12") (pintype "input"))
      (node (ref "IC9") (pin "3") (pinfunction "+IN_3") (pintype "input"))
      (node (ref "IC9") (pin "5") (pinfunction "+IN_5") (pintype "input"))
      (node (ref "J1") (pin "P1") (pinfunction "1_P1") (pintype "passive"))
      (node (ref "J2") (pin "P1") (pinfunction "1_P1") (pintype "passive"))
      (node (ref "J3") (pin "P1") (pinfunction "1_P1") (pintype "passive"))
      (node (ref "J4") (pin "P1") (pinfunction "1_P1") (pintype "passive"))
      (node (ref "J5") (pin "P1") (pinfunction "1_P1") (pintype "passive"))
      (node (ref "J6") (pin "P1") (pinfunction "1_P1") (pintype "passive"))
      (node (ref "JP1") (pin "3") (pinfunction "3_3") (pintype "passive"))
      (node (ref "JP1") (pin "4") (pinfunction "4_4") (pintype "passive"))
      (node (ref "JP1") (pin "5") (pinfunction "5_5") (pintype "passive"))
      (node (ref "JP1") (pin "6") (pinfunction "6_6") (pintype "passive"))
      (node (ref "JP1") (pin "7") (pinfunction "7_7") (pintype "passive"))
      (node (ref "JP1") (pin "8") (pinfunction "8_8") (pintype "passive"))
      (node (ref "JP2") (pin "3") (pinfunction "3_3") (pintype "passive"))
      (node (ref "JP2") (pin "5") (pinfunction "5_5") (pintype "passive"))
      (node (ref "JP2") (pin "9") (pinfunction "9_9") (pintype "passive"))
      (node (ref "JP3") (pin "1") (pinfunction "1_1") (pintype "passive"))
      (node (ref "Q1") (pin "E") (pinfunction "E_E") (pintype "passive"))
      (node (ref "Q2") (pin "E") (pinfunction "E_E") (pintype "passive"))
      (node (ref "Q3") (pin "E") (pinfunction "E_E") (pintype "passive"))
      (node (ref "Q4") (pin "E") (pinfunction "E_E") (pintype "passive"))
      (node (ref "Q6") (pin "E") (pinfunction "E_E") (pintype "passive"))
      (node (ref "R19") (pin "P$3") (pinfunction "A_P$3") (pintype "passive"))
      (node (ref "R20") (pin "P$3") (pinfunction "A_P$3") (pintype "passive"))
      (node (ref "R33") (pin "1") (pinfunction "1_1") (pintype "passive"))
      (node (ref "R36") (pin "P$3") (pinfunction "A_P$3") (pintype "passive"))
      (node (ref "R38") (pin "P$3") (pinfunction "A_P$3") (pintype "passive"))
      (node (ref "SW1") (pin "C") (pinfunction "C_C") (pintype "passive"))
      (node (ref "SW1") (pin "D") (pinfunction "1_D") (pintype "passive"))
      (node (ref "SW2") (pin "A") (pinfunction "P_A") (pintype "passive"))
      (node (ref "SW2") (pin "A'") (pinfunction "P1_A'") (pintype "passive"))
      (node (ref "UC1") (pin "20") (pinfunction "PB2/BOOT1_20") (pintype "bidirectional"))
      (node (ref "UC1") (pin "23") (pinfunction "VSS_1_23") (pintype "power_in"))
      (node (ref "UC1") (pin "35") (pinfunction "VSS_2_35") (pintype "power_in"))
      (node (ref "UC1") (pin "46") (pinfunction "PB9/TIM4_CH4_46") (pintype "input"))
      (node (ref "UC1") (pin "47") (pinfunction "VSS_3_47") (pintype "power_in"))
      (node (ref "UC1") (pin "8") (pinfunction "VSS_A_8") (pintype "power_in"))
    )
    (net (code "27") (name "JTCK") (class "Default")
      (node (ref "JP2") (pin "4") (pinfunction "4_4") (pintype "passive"))
      (node (ref "UC1") (pin "37") (pinfunction "PA14/JTCK/SWCLK_37") (pintype "bidirectional"))
    )
    (net (code "28") (name "JTDI") (class "Default")
      (node (ref "JP2") (pin "8") (pinfunction "8_8") (pintype "passive"))
      (node (ref "UC1") (pin "38") (pinfunction "PA15/JTDI_38") (pintype "bidirectional"))
    )
    (net (code "29") (name "JTDO") (class "Default")
      (node (ref "JP2") (pin "6") (pinfunction "6_6") (pintype "passive"))
      (node (ref "UC1") (pin "39") (pinfunction "PB3/JTDO_39") (pintype "bidirectional"))
    )
    (net (code "30") (name "JTMS") (class "Default")
      (node (ref "JP2") (pin "2") (pinfunction "2_2") (pintype "passive"))
      (node (ref "UC1") (pin "34") (pinfunction "PA13/JTMS/SWDIO_34") (pintype "bidirectional"))
    )
    (net (code "31") (name "Net-(C21-Pad1)") (class "Default")
      (node (ref "C21") (pin "1") (pinfunction "1_1") (pintype "passive"))
      (node (ref "R45") (pin "1") (pinfunction "1_1") (pintype "passive"))
      (node (ref "R46") (pin "2") (pinfunction "2_2") (pintype "passive"))
    )
    (net (code "32") (name "Net-(C24-Pad-)") (class "Default")
      (node (ref "C24") (pin "-") (pinfunction "-_-") (pintype "passive"))
      (node (ref "R50") (pin "2") (pinfunction "2_2") (pintype "passive"))
    )
    (net (code "33") (name "Net-(D1-PadA)") (class "Default")
      (node (ref "D1") (pin "A") (pinfunction "A_A") (pintype "passive"))
      (node (ref "JP1") (pin "1") (pinfunction "1_1") (pintype "passive"))
      (node (ref "JP1") (pin "2") (pinfunction "2_2") (pintype "passive"))
    )
    (net (code "34") (name "Net-(D2-PadC)") (class "Default")
      (node (ref "D2") (pin "C") (pinfunction "C_C") (pintype "passive"))
      (node (ref "JP1") (pin "10") (pinfunction "10_10") (pintype "passive"))
      (node (ref "JP1") (pin "9") (pinfunction "9_9") (pintype "passive"))
    )
    (net (code "35") (name "Net-(DISP1-A)") (class "Default")
      (node (ref "DISP1") (pin "12") (pinfunction "A_12") (pintype "passive"))
      (node (ref "DISP2") (pin "12") (pinfunction "A_12") (pintype "passive"))
      (node (ref "R9") (pin "2") (pinfunction "2_2") (pintype "passive"))
    )
    (net (code "36") (name "Net-(DISP1-B)") (class "Default")
      (node (ref "DISP1") (pin "10") (pinfunction "B_10") (pintype "passive"))
      (node (ref "DISP2") (pin "10") (pinfunction "B_10") (pintype "passive"))
      (node (ref "R10") (pin "2") (pinfunction "2_2") (pintype "passive"))
    )
    (net (code "37") (name "Net-(DISP1-C)") (class "Default")
      (node (ref "DISP1") (pin "9") (pinfunction "C_9") (pintype "passive"))
      (node (ref "DISP2") (pin "9") (pinfunction "C_9") (pintype "passive"))
      (node (ref "R12") (pin "2") (pinfunction "2_2") (pintype "passive"))
    )
    (net (code "38") (name "Net-(DISP1-D)") (class "Default")
      (node (ref "DISP1") (pin "7") (pinfunction "D_7") (pintype "passive"))
      (node (ref "DISP2") (pin "7") (pinfunction "D_7") (pintype "passive"))
      (node (ref "R18") (pin "2") (pinfunction "2_2") (pintype "passive"))
    )
    (net (code "39") (name "Net-(DISP1-E)") (class "Default")
      (node (ref "DISP1") (pin "1") (pinfunction "E_1") (pintype "passive"))
      (node (ref "DISP2") (pin "1") (pinfunction "E_1") (pintype "passive"))
      (node (ref "R13") (pin "2") (pinfunction "2_2") (pintype "passive"))
    )
    (net (code "40") (name "Net-(DISP1-F)") (class "Default")
      (node (ref "DISP1") (pin "18") (pinfunction "F_18") (pintype "passive"))
      (node (ref "DISP2") (pin "18") (pinfunction "F_18") (pintype "passive"))
      (node (ref "R4") (pin "2") (pinfunction "2_2") (pintype "passive"))
    )
    (net (code "41") (name "Net-(DISP1-G)") (class "Default")
      (node (ref "DISP1") (pin "17") (pinfunction "G_17") (pintype "passive"))
      (node (ref "DISP2") (pin "17") (pinfunction "G_17") (pintype "passive"))
      (node (ref "R5") (pin "2") (pinfunction "2_2") (pintype "passive"))
    )
    (net (code "42") (name "Net-(DISP1-H)") (class "Default")
      (node (ref "DISP1") (pin "15") (pinfunction "H_15") (pintype "passive"))
      (node (ref "DISP2") (pin "15") (pinfunction "H_15") (pintype "passive"))
      (node (ref "R6") (pin "2") (pinfunction "2_2") (pintype "passive"))
    )
    (net (code "43") (name "Net-(DISP1-J)") (class "Default")
      (node (ref "DISP1") (pin "14") (pinfunction "J_14") (pintype "passive"))
      (node (ref "DISP2") (pin "14") (pinfunction "J_14") (pintype "passive"))
      (node (ref "R7") (pin "2") (pinfunction "2_2") (pintype "passive"))
    )
    (net (code "44") (name "Net-(DISP1-K)") (class "Default")
      (node (ref "DISP1") (pin "6") (pinfunction "K_6") (pintype "passive"))
      (node (ref "DISP2") (pin "6") (pinfunction "K_6") (pintype "passive"))
      (node (ref "R17") (pin "2") (pinfunction "2_2") (pintype "passive"))
    )
    (net (code "45") (name "Net-(DISP1-K1)") (class "Default")
      (node (ref "DISP1") (pin "16") (pinfunction "K1_16") (pintype "passive"))
      (node (ref "Q1") (pin "C") (pinfunction "C_C") (pintype "passive"))
    )
    (net (code "46") (name "Net-(DISP1-K2)") (class "Default")
      (node (ref "DISP1") (pin "11") (pinfunction "K2_11") (pintype "passive"))
      (node (ref "Q2") (pin "C") (pinfunction "C_C") (pintype "passive"))
    )
    (net (code "47") (name "Net-(DISP1-L)") (class "Default")
      (node (ref "DISP1") (pin "5") (pinfunction "L_5") (pintype "passive"))
      (node (ref "DISP2") (pin "5") (pinfunction "L_5") (pintype "passive"))
      (node (ref "R16") (pin "2") (pinfunction "2_2") (pintype "passive"))
    )
    (net (code "48") (name "Net-(DISP1-M)") (class "Default")
      (node (ref "DISP1") (pin "4") (pinfunction "M_4") (pintype "passive"))
      (node (ref "DISP2") (pin "4") (pinfunction "M_4") (pintype "passive"))
      (node (ref "R15") (pin "2") (pinfunction "2_2") (pintype "passive"))
    )
    (net (code "49") (name "Net-(DISP1-N)") (class "Default")
      (node (ref "DISP1") (pin "2") (pinfunction "N_2") (pintype "passive"))
      (node (ref "DISP2") (pin "2") (pinfunction "N_2") (pintype "passive"))
      (node (ref "R14") (pin "2") (pinfunction "2_2") (pintype "passive"))
    )
    (net (code "50") (name "Net-(DISP1-P)") (class "Default")
      (node (ref "DISP1") (pin "13") (pinfunction "P_13") (pintype "passive"))
      (node (ref "DISP2") (pin "13") (pinfunction "P_13") (pintype "passive"))
      (node (ref "R8") (pin "2") (pinfunction "2_2") (pintype "passive"))
    )
    (net (code "51") (name "Net-(DISP2-K1)") (class "Default")
      (node (ref "DISP2") (pin "16") (pinfunction "K1_16") (pintype "passive"))
      (node (ref "Q3") (pin "C") (pinfunction "C_C") (pintype "passive"))
    )
    (net (code "52") (name "Net-(DISP2-K2)") (class "Default")
      (node (ref "DISP2") (pin "11") (pinfunction "K2_11") (pintype "passive"))
      (node (ref "Q4") (pin "C") (pinfunction "C_C") (pintype "passive"))
    )
    (net (code "53") (name "Net-(IC1A-QA)") (class "Default")
      (node (ref "IC1") (pin "15") (pinfunction "QA_15") (pintype "tri_state"))
      (node (ref "R7") (pin "1") (pinfunction "1_1") (pintype "passive"))
    )
    (net (code "54") (name "Net-(IC1A-QB)") (class "Default")
      (node (ref "IC1") (pin "1") (pinfunction "QB_1") (pintype "tri_state"))
      (node (ref "R17") (pin "1") (pinfunction "1_1") (pintype "passive"))
    )
    (net (code "55") (name "Net-(IC1A-QC)") (class "Default")
      (node (ref "IC1") (pin "2") (pinfunction "QC_2") (pintype "tri_state"))
      (node (ref "R16") (pin "1") (pinfunction "1_1") (pintype "passive"))
    )
    (net (code "56") (name "Net-(IC1A-QD)") (class "Default")
      (node (ref "IC1") (pin "3") (pinfunction "QD_3") (pintype "tri_state"))
      (node (ref "R15") (pin "1") (pinfunction "1_1") (pintype "passive"))
    )
    (net (code "57") (name "Net-(IC1A-QE)") (class "Default")
      (node (ref "IC1") (pin "4") (pinfunction "QE_4") (pintype "tri_state"))
      (node (ref "R14") (pin "1") (pinfunction "1_1") (pintype "passive"))
    )
    (net (code "58") (name "Net-(IC1A-QF)") (class "Default")
      (node (ref "IC1") (pin "5") (pinfunction "QF_5") (pintype "tri_state"))
      (node (ref "R8") (pin "1") (pinfunction "1_1") (pintype "passive"))
    )
    (net (code "59") (name "Net-(IC1A-SER)") (class "Default")
      (node (ref "IC1") (pin "14") (pinfunction "SER_14") (pintype "input"))
      (node (ref "IC2") (pin "9") (pinfunction "QH*_9") (pintype "tri_state"))
    )
    (net (code "60") (name "Net-(IC2A-QA)") (class "Default")
      (node (ref "IC2") (pin "15") (pinfunction "QA_15") (pintype "tri_state"))
      (node (ref "R9") (pin "1") (pinfunction "1_1") (pintype "passive"))
    )
    (net (code "61") (name "Net-(IC2A-QB)") (class "Default")
      (node (ref "IC2") (pin "1") (pinfunction "QB_1") (pintype "tri_state"))
      (node (ref "R10") (pin "1") (pinfunction "1_1") (pintype "passive"))
    )
    (net (code "62") (name "Net-(IC2A-QC)") (class "Default")
      (node (ref "IC2") (pin "2") (pinfunction "QC_2") (pintype "tri_state"))
      (node (ref "R12") (pin "1") (pinfunction "1_1") (pintype "passive"))
    )
    (net (code "63") (name "Net-(IC2A-QD)") (class "Default")
      (node (ref "IC2") (pin "3") (pinfunction "QD_3") (pintype "tri_state"))
      (node (ref "R18") (pin "1") (pinfunction "1_1") (pintype "passive"))
    )
    (net (code "64") (name "Net-(IC2A-QE)") (class "Default")
      (node (ref "IC2") (pin "4") (pinfunction "QE_4") (pintype "tri_state"))
      (node (ref "R13") (pin "1") (pinfunction "1_1") (pintype "passive"))
    )
    (net (code "65") (name "Net-(IC2A-QF)") (class "Default")
      (node (ref "IC2") (pin "5") (pinfunction "QF_5") (pintype "tri_state"))
      (node (ref "R4") (pin "1") (pinfunction "1_1") (pintype "passive"))
    )
    (net (code "66") (name "Net-(IC2A-QG)") (class "Default")
      (node (ref "IC2") (pin "6") (pinfunction "QG_6") (pintype "tri_state"))
      (node (ref "R5") (pin "1") (pinfunction "1_1") (pintype "passive"))
    )
    (net (code "67") (name "Net-(IC2A-QH)") (class "Default")
      (node (ref "IC2") (pin "7") (pinfunction "QH_7") (pintype "tri_state"))
      (node (ref "R6") (pin "1") (pinfunction "1_1") (pintype "passive"))
    )
    (net (code "68") (name "Net-(IC6-VIN)") (class "Default")
      (node (ref "C19") (pin "+") (pinfunction "+_+") (pintype "passive"))
      (node (ref "IC6") (pin "2") (pinfunction "VIN_2") (pintype "input"))
      (node (ref "R49") (pin "1") (pinfunction "1_1") (pintype "passive"))
    )
    (net (code "69") (name "Net-(IC7A--IN)") (class "Default")
      (node (ref "C16") (pin "1") (pinfunction "1_1") (pintype "passive"))
      (node (ref "IC7") (pin "2") (pinfunction "-IN_2") (pintype "input"))
      (node (ref "R34") (pin "1") (pinfunction "1_1") (pintype "passive"))
      (node (ref "R39") (pin "2") (pinfunction "2_2") (pintype "passive"))
      (node (ref "R41") (pin "2") (pinfunction "2_2") (pintype "passive"))
    )
    (net (code "70") (name "Net-(IC7B--IN)") (class "Default")
      (node (ref "C17") (pin "1") (pinfunction "1_1") (pintype "passive"))
      (node (ref "IC7") (pin "6") (pinfunction "-IN_6") (pintype "input"))
      (node (ref "R21") (pin "P$3") (pinfunction "A_P$3") (pintype "passive"))
      (node (ref "R35") (pin "1") (pinfunction "1_1") (pintype "passive"))
      (node (ref "R40") (pin "2") (pinfunction "2_2") (pintype "passive"))
      (node (ref "R42") (pin "2") (pinfunction "2_2") (pintype "passive"))
    )
    (net (code "71") (name "Net-(IC7C--IN)") (class "Default")
      (node (ref "C14") (pin "1") (pinfunction "1_1") (pintype "passive"))
      (node (ref "IC7") (pin "9") (pinfunction "-IN_9") (pintype "input"))
      (node (ref "R26") (pin "1") (pinfunction "1_1") (pintype "passive"))
      (node (ref "R31") (pin "2") (pinfunction "2_2") (pintype "passive"))
      (node (ref "R32") (pin "2") (pinfunction "2_2") (pintype "passive"))
    )
    (net (code "72") (name "Net-(IC7D--IN)") (class "Default")
      (node (ref "C13") (pin "1") (pinfunction "1_1") (pintype "passive"))
      (node (ref "IC7") (pin "13") (pinfunction "-IN_13") (pintype "input"))
      (node (ref "R25") (pin "1") (pinfunction "1_1") (pintype "passive"))
      (node (ref "R28") (pin "2") (pinfunction "2_2") (pintype "passive"))
      (node (ref "R30") (pin "2") (pinfunction "2_2") (pintype "passive"))
      (node (ref "R37") (pin "P$3") (pinfunction "A_P$3") (pintype "passive"))
    )
    (net (code "73") (name "Net-(IC9A--IN)") (class "Default")
      (node (ref "IC9") (pin "2") (pinfunction "-IN_2") (pintype "input"))
      (node (ref "R21") (pin "P$1") (pinfunction "E_P$1") (pintype "passive"))
      (node (ref "R52") (pin "1") (pinfunction "1_1") (pintype "passive"))
    )
    (net (code "74") (name "Net-(IC9A-OUT)") (class "Default")
      (node (ref "IC9") (pin "1") (pinfunction "OUT_1") (pintype "output"))
      (node (ref "R42") (pin "1") (pinfunction "1_1") (pintype "passive"))
      (node (ref "R52") (pin "2") (pinfunction "2_2") (pintype "passive"))
    )
    (net (code "75") (name "Net-(IC9B--IN)") (class "Default")
      (node (ref "IC9") (pin "6") (pinfunction "-IN_6") (pintype "input"))
      (node (ref "R53") (pin "1") (pinfunction "1_1") (pintype "passive"))
      (node (ref "R54") (pin "2") (pinfunction "2_2") (pintype "passive"))
    )
    (net (code "76") (name "Net-(IC9B-OUT)") (class "Default")
      (node (ref "IC9") (pin "7") (pinfunction "OUT_7") (pintype "output"))
      (node (ref "R41") (pin "1") (pinfunction "1_1") (pintype "passive"))
      (node (ref "R53") (pin "2") (pinfunction "2_2") (pintype "passive"))
    )
    (net (code "77") (name "Net-(IC9C--IN)") (class "Default")
      (node (ref "IC9") (pin "9") (pinfunction "-IN_9") (pintype "input"))
      (node (ref "R44") (pin "1") (pinfunction "1_1") (pintype "passive"))
      (node (ref "R47") (pin "2") (pinfunction "2_2") (pintype "passive"))
    )
    (net (code "78") (name "Net-(IC9C-OUT)") (class "Default")
      (node (ref "IC9") (pin "8") (pinfunction "OUT_8") (pintype "output"))
      (node (ref "R31") (pin "1") (pinfunction "1_1") (pintype "passive"))
      (node (ref "R44") (pin "2") (pinfunction "2_2") (pintype "passive"))
    )
    (net (code "79") (name "Net-(IC9D--IN)") (class "Default")
      (node (ref "IC9") (pin "13") (pinfunction "-IN_13") (pintype "input"))
      (node (ref "R37") (pin "P$1") (pinfunction "E_P$1") (pintype "passive"))
      (node (ref "R43") (pin "1") (pinfunction "1_1") (pintype "passive"))
    )
    (net (code "80") (name "Net-(IC9D-OUT)") (class "Default")
      (node (ref "IC9") (pin "14") (pinfunction "OUT_14") (pintype "output"))
      (node (ref "R30") (pin "1") (pinfunction "1_1") (pintype "passive"))
      (node (ref "R43") (pin "2") (pinfunction "2_2") (pintype "passive"))
    )
    (net (code "81") (name "Net-(IC10A--IN)") (class "Default")
      (node (ref "C29") (pin "1") (pinfunction "1_1") (pintype "passive"))
      (node (ref "IC10") (pin "2") (pinfunction "-IN_2") (pintype "input"))
      (node (ref "R50") (pin "1") (pinfunction "1_1") (pintype "passive"))
      (node (ref "R56") (pin "2") (pinfunction "2_2") (pintype "passive"))
    )
    (net (code "82") (name "Net-(IC10A-OUT)") (class "Default")
      (node (ref "C29") (pin "2") (pinfunction "2_2") (pintype "passive"))
      (node (ref "IC10") (pin "1") (pinfunction "OUT_1") (pintype "output"))
      (node (ref "R55") (pin "2") (pinfunction "2_2") (pintype "passive"))
    )
    (net (code "83") (name "Net-(IC10B-+IN)") (class "Default")
      (node (ref "C22") (pin "1") (pinfunction "1_1") (pintype "passive"))
      (node (ref "IC10") (pin "5") (pinfunction "+IN_5") (pintype "input"))
      (node (ref "R46") (pin "1") (pinfunction "1_1") (pintype "passive"))
    )
    (net (code "84") (name "Net-(IC10B--IN)") (class "Default")
      (node (ref "C21") (pin "2") (pinfunction "2_2") (pintype "passive"))
      (node (ref "C24") (pin "+") (pinfunction "+_+") (pintype "passive"))
      (node (ref "IC10") (pin "6") (pinfunction "-IN_6") (pintype "input"))
      (node (ref "IC10") (pin "7") (pinfunction "OUT_7") (pintype "output"))
    )
    (net (code "85") (name "Net-(J1-3)") (class "Default")
      (node (ref "J1") (pin "P3") (pinfunction "3_P3") (pintype "passive"))
      (node (ref "R29") (pin "1") (pinfunction "1_1") (pintype "passive"))
    )
    (net (code "86") (name "Net-(J2-3)") (class "Default")
      (node (ref "J2") (pin "P3") (pinfunction "3_P3") (pintype "passive"))
      (node (ref "R54") (pin "1") (pinfunction "1_1") (pintype "passive"))
    )
    (net (code "87") (name "Net-(J3-3)") (class "Default")
      (node (ref "J3") (pin "P3") (pinfunction "3_P3") (pintype "passive"))
      (node (ref "R24") (pin "1") (pinfunction "1_1") (pintype "passive"))
    )
    (net (code "88") (name "Net-(J4-3)") (class "Default")
      (node (ref "J4") (pin "P3") (pinfunction "3_P3") (pintype "passive"))
      (node (ref "R48") (pin "1") (pinfunction "1_1") (pintype "passive"))
    )
    (net (code "89") (name "Net-(J5-3)") (class "Default")
      (node (ref "J5") (pin "P3") (pinfunction "3_P3") (pintype "passive"))
      (node (ref "R47") (pin "1") (pinfunction "1_1") (pintype "passive"))
    )
    (net (code "90") (name "Net-(J6-3)") (class "Default")
      (node (ref "J6") (pin "P3") (pinfunction "3_P3") (pintype "passive"))
      (node (ref "R55") (pin "1") (pinfunction "1_1") (pintype "passive"))
      (node (ref "R56") (pin "1") (pinfunction "1_1") (pintype "passive"))
    )
    (net (code "91") (name "Net-(Q1-PadB)") (class "Default")
      (node (ref "Q1") (pin "B") (pinfunction "B_B") (pintype "passive"))
      (node (ref "R1") (pin "2") (pinfunction "2_2") (pintype "passive"))
    )
    (net (code "92") (name "Net-(Q2-PadB)") (class "Default")
      (node (ref "Q2") (pin "B") (pinfunction "B_B") (pintype "passive"))
      (node (ref "R2") (pin "2") (pinfunction "2_2") (pintype "passive"))
    )
    (net (code "93") (name "Net-(Q3-PadB)") (class "Default")
      (node (ref "Q3") (pin "B") (pinfunction "B_B") (pintype "passive"))
      (node (ref "R3") (pin "2") (pinfunction "2_2") (pintype "passive"))
    )
    (net (code "94") (name "Net-(Q4-PadB)") (class "Default")
      (node (ref "Q4") (pin "B") (pinfunction "B_B") (pintype "passive"))
      (node (ref "R11") (pin "2") (pinfunction "2_2") (pintype "passive"))
    )
    (net (code "95") (name "Net-(Q6-PadB)") (class "Default")
      (node (ref "Q6") (pin "B") (pinfunction "B_B") (pintype "passive"))
      (node (ref "R29") (pin "2") (pinfunction "2_2") (pintype "passive"))
    )
    (net (code "96") (name "Net-(R20-S)") (class "Default")
      (node (ref "R20") (pin "P$2") (pinfunction "S_P$2") (pintype "passive"))
      (node (ref "R39") (pin "1") (pinfunction "1_1") (pintype "passive"))
    )
    (net (code "97") (name "Net-(R21-S)") (class "Default")
      (node (ref "R21") (pin "P$2") (pinfunction "S_P$2") (pintype "passive"))
      (node (ref "R24") (pin "2") (pinfunction "2_2") (pintype "passive"))
    )
    (net (code "98") (name "Net-(R36-S)") (class "Default")
      (node (ref "R28") (pin "1") (pinfunction "1_1") (pintype "passive"))
      (node (ref "R36") (pin "P$2") (pinfunction "S_P$2") (pintype "passive"))
    )
    (net (code "99") (name "Net-(R37-S)") (class "Default")
      (node (ref "R37") (pin "P$2") (pinfunction "S_P$2") (pintype "passive"))
      (node (ref "R48") (pin "2") (pinfunction "2_2") (pintype "passive"))
    )
    (net (code "100") (name "Net-(R38-S)") (class "Default")
      (node (ref "R32") (pin "1") (pinfunction "1_1") (pintype "passive"))
      (node (ref "R38") (pin "P$2") (pinfunction "S_P$2") (pintype "passive"))
    )
    (net (code "101") (name "Net-(UC1-PD0-OSC_IN)") (class "Default")
      (node (ref "C9") (pin "2") (pinfunction "2_2") (pintype "passive"))
      (node (ref "Q5") (pin "2") (pinfunction "2_2") (pintype "passive"))
      (node (ref "UC1") (pin "5") (pinfunction "PD0-OSC_IN_5") (pintype "input"))
    )
    (net (code "102") (name "Net-(UC1-PD1-OSC_OUT)") (class "Default")
      (node (ref "C10") (pin "2") (pinfunction "2_2") (pintype "passive"))
      (node (ref "Q5") (pin "1") (pinfunction "1_1") (pintype "passive"))
      (node (ref "UC1") (pin "6") (pinfunction "PD1-OSC_OUT_6") (pintype "input"))
    )
    (net (code "103") (name "PARAM1_CV") (class "Default")
      (node (ref "C13") (pin "2") (pinfunction "2_2") (pintype "passive"))
      (node (ref "IC4") (pin "1") (pinfunction "CH0_1") (pintype "bidirectional"))
      (node (ref "IC7") (pin "14") (pinfunction "OUT_14") (pintype "output"))
      (node (ref "R25") (pin "2") (pinfunction "2_2") (pintype "passive"))
    )
    (net (code "104") (name "PARAM2_CV") (class "Default")
      (node (ref "C14") (pin "2") (pinfunction "2_2") (pintype "passive"))
      (node (ref "IC4") (pin "2") (pinfunction "CH1_2") (pintype "bidirectional"))
      (node (ref "IC7") (pin "8") (pinfunction "OUT_8") (pintype "output"))
      (node (ref "R26") (pin "2") (pinfunction "2_2") (pintype "passive"))
    )
    (net (code "105") (name "PITCH_CV") (class "Default")
      (node (ref "C16") (pin "2") (pinfunction "2_2") (pintype "passive"))
      (node (ref "IC4") (pin "3") (pinfunction "CH2_3") (pintype "bidirectional"))
      (node (ref "IC7") (pin "1") (pinfunction "OUT_1") (pintype "output"))
      (node (ref "R34") (pin "2") (pinfunction "2_2") (pintype "passive"))
    )
    (net (code "106") (name "RESET") (class "Default")
      (node (ref "JP2") (pin "10") (pinfunction "10_10") (pintype "passive"))
      (node (ref "R22") (pin "1") (pinfunction "1_1") (pintype "passive"))
      (node (ref "SW2") (pin "B") (pinfunction "S_B") (pintype "passive"))
      (node (ref "SW2") (pin "B'") (pinfunction "S1_B'") (pintype "passive"))
      (node (ref "UC1") (pin "7") (pinfunction "NRST_7") (pintype "input"))
    )
    (net (code "107") (name "RX") (class "Default")
      (node (ref "JP3") (pin "4") (pinfunction "4_4") (pintype "passive"))
      (node (ref "UC1") (pin "31") (pinfunction "PA10/USART1_RX/TIM1_CH3_31") (pintype "bidirectional"))
    )
    (net (code "108") (name "TX") (class "Default")
      (node (ref "JP3") (pin "5") (pinfunction "5_5") (pintype "passive"))
      (node (ref "UC1") (pin "30") (pinfunction "PA9/USART1_TX/TIM1_CH2_30") (pintype "input"))
    )
    (net (code "109") (name "VCC") (class "Default")
      (node (ref "C23") (pin "1") (pinfunction "1_1") (pintype "passive"))
      (node (ref "C25") (pin "+") (pinfunction "+_+") (pintype "passive"))
      (node (ref "C28") (pin "1") (pinfunction "1_1") (pintype "passive"))
      (node (ref "D1") (pin "C") (pinfunction "C_C") (pintype "passive"))
      (node (ref "IC10") (pin "8") (pinfunction "V+_8") (pintype "power_in"))
      (node (ref "IC9") (pin "4") (pinfunction "V+_4") (pintype "power_in"))
      (node (ref "R49") (pin "2") (pinfunction "2_2") (pintype "passive"))
    )
    (net (code "110") (name "VEE") (class "Default")
      (node (ref "C20") (pin "2") (pinfunction "2_2") (pintype "passive"))
      (node (ref "C27") (pin "2") (pinfunction "2_2") (pintype "passive"))
      (node (ref "C30") (pin "-") (pinfunction "-_-") (pintype "passive"))
      (node (ref "D2") (pin "A") (pinfunction "A_A") (pintype "passive"))
      (node (ref "IC10") (pin "4") (pinfunction "V-_4") (pintype "power_in"))
      (node (ref "IC9") (pin "11") (pinfunction "V-_11") (pintype "power_in"))
      (node (ref "R51") (pin "1") (pinfunction "1_1") (pintype "passive"))
    )
    (net (code "111") (name "unconnected-(DISP1-DP-Pad8)") (class "Default")
      (node (ref "DISP1") (pin "8") (pinfunction "DP_8") (pintype "passive"))
    )
    (net (code "112") (name "unconnected-(DISP2-DP-Pad8)") (class "Default")
      (node (ref "DISP2") (pin "8") (pinfunction "DP_8") (pintype "passive"))
    )
    (net (code "113") (name "unconnected-(IC1A-QG-Pad6)") (class "Default")
      (node (ref "IC1") (pin "6") (pinfunction "QG_6") (pintype "tri_state"))
    )
    (net (code "114") (name "unconnected-(IC1A-QH*-Pad9)") (class "Default")
      (node (ref "IC1") (pin "9") (pinfunction "QH*_9") (pintype "tri_state"))
    )
    (net (code "115") (name "unconnected-(IC1A-QH-Pad7)") (class "Default")
      (node (ref "IC1") (pin "7") (pinfunction "QH_7") (pintype "tri_state"))
    )
    (net (code "116") (name "unconnected-(J1-2-PadP2)") (class "Default")
      (node (ref "J1") (pin "P2") (pinfunction "2_P2") (pintype "passive"))
    )
    (net (code "117") (name "unconnected-(J2-2-PadP2)") (class "Default")
      (node (ref "J2") (pin "P2") (pinfunction "2_P2") (pintype "passive"))
    )
    (net (code "118") (name "unconnected-(J3-2-PadP2)") (class "Default")
      (node (ref "J3") (pin "P2") (pinfunction "2_P2") (pintype "passive"))
    )
    (net (code "119") (name "unconnected-(J4-2-PadP2)") (class "Default")
      (node (ref "J4") (pin "P2") (pinfunction "2_P2") (pintype "passive"))
    )
    (net (code "120") (name "unconnected-(J5-2-PadP2)") (class "Default")
      (node (ref "J5") (pin "P2") (pinfunction "2_P2") (pintype "passive"))
    )
    (net (code "121") (name "unconnected-(J6-2-PadP2)") (class "Default")
      (node (ref "J6") (pin "P2") (pinfunction "2_P2") (pintype "passive"))
    )
    (net (code "122") (name "unconnected-(JP2-Pad7)") (class "Default")
      (node (ref "JP2") (pin "7") (pinfunction "7_7") (pintype "passive"))
    )
    (net (code "123") (name "unconnected-(JP3-Pad2)") (class "Default")
      (node (ref "JP3") (pin "2") (pinfunction "2_2") (pintype "passive"))
    )
    (net (code "124") (name "unconnected-(JP3-Pad3)") (class "Default")
      (node (ref "JP3") (pin "3") (pinfunction "3_3") (pintype "passive"))
    )
    (net (code "125") (name "unconnected-(JP3-Pad6)") (class "Default")
      (node (ref "JP3") (pin "6") (pinfunction "6_6") (pintype "passive"))
    )
    (net (code "126") (name "unconnected-(UC1-PA0_WKUP{slash}USART2_CTS{slash}ADC12_IN0{slash}TIM2_CH1_ETR-Pad10)") (class "Default")
      (node (ref "UC1") (pin "10") (pinfunction "PA0_WKUP/USART2_CTS/ADC12_IN0/TIM2_CH1_ETR_10") (pintype "bidirectional"))
    )
    (net (code "127") (name "unconnected-(UC1-PA1{slash}USART2_RTS{slash}ADC12_IN1{slash}TIM2_CH2-Pad11)") (class "Default")
      (node (ref "UC1") (pin "11") (pinfunction "PA1/USART2_RTS/ADC12_IN1/TIM2_CH2_11") (pintype "bidirectional"))
    )
    (net (code "128") (name "unconnected-(UC1-PA2{slash}USART2_TX{slash}ADC12_IN2{slash}TIM2_CH3-Pad12)") (class "Default")
      (node (ref "UC1") (pin "12") (pinfunction "PA2/USART2_TX/ADC12_IN2/TIM2_CH3_12") (pintype "bidirectional"))
    )
    (net (code "129") (name "unconnected-(UC1-PA8{slash}USART1_CK{slash}TIM1_CH1{slash}MCO-Pad29)") (class "Default")
      (node (ref "UC1") (pin "29") (pinfunction "PA8/USART1_CK/TIM1_CH1/MCO_29") (pintype "bidirectional"))
    )
    (net (code "130") (name "unconnected-(UC1-PA11{slash}USART1_CTS{slash}CAN_RX{slash}TIM1_CH4{slash}USBDM-Pad32)") (class "Default")
      (node (ref "UC1") (pin "32") (pinfunction "PA11/USART1_CTS/CAN_RX/TIM1_CH4/USBDM_32") (pintype "bidirectional"))
    )
    (net (code "131") (name "unconnected-(UC1-PA12{slash}USART1_RTS{slash}CAN_TX{slash}TIM1_ETR{slash}USBDP-Pad33)") (class "Default")
      (node (ref "UC1") (pin "33") (pinfunction "PA12/USART1_RTS/CAN_TX/TIM1_ETR/USBDP_33") (pintype "bidirectional"))
    )
    (net (code "132") (name "unconnected-(UC1-PB4{slash}NJTRST-Pad40)") (class "Default")
      (node (ref "UC1") (pin "40") (pinfunction "PB4/NJTRST_40") (pintype "bidirectional"))
    )
    (net (code "133") (name "unconnected-(UC1-PB14{slash}SPI2_MISO{slash}USART3_RTS{slash}TIM1_CH2N-Pad27)") (class "Default")
      (node (ref "UC1") (pin "27") (pinfunction "PB14/SPI2_MISO/USART3_RTS/TIM1_CH2N_27") (pintype "input"))
    )
  )
)
